# MOTORES.net
KiCad netlist of a schematic drawn in Altium Designer
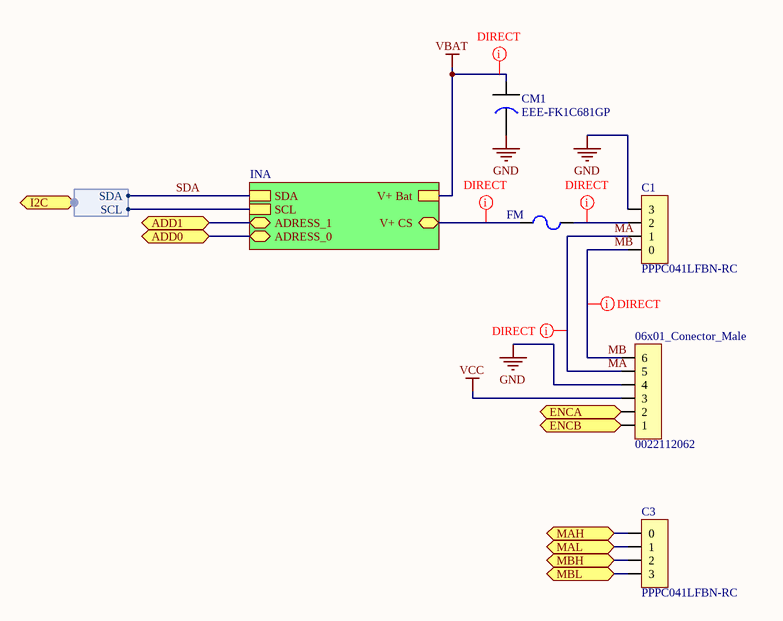
[diagram p0: MOTORES.SchDoc]

(export (version "E")
  (design (tool "Eeschema 10.0.6"))
  (components
    (comp (ref "06x01_Conector_Male")
      (value "0022112062")
      (footprint "06x01_Conector_Male")
      (description "CONN HEADER 6POS .100 VERT GOLD")
      (libsource (lib "Schlib1") (part "06x01_Conector_Male"))
    )
    (comp (ref "C1")
      (value "PPPC041LFBN-RC")
      (footprint "04x01_Conector_Female")
      (description "4 Position Header Connector 0.100\" (2.54mm) Through Hole Gold")
      (libsource (lib "Schlib1") (part "04x01_Conector_Female-SCH"))
    )
    (comp (ref "C3")
      (value "PPPC041LFBN-RC")
      (footprint "04x01_Conector_Female")
      (description "4 Position Header Connector 0.100\" (2.54mm) Through Hole Gold")
      (libsource (lib "") (part "04x01_Conector_Female-SCH_1"))
    )
    (comp (ref "CM1")
      (value "EEE-FK1C681GP")
      (footprint "EEE-FK1C681GP")
      (description "Aluminum Electrolytic Capacitors - SMD Al Lytic Cap SMT FK Series 105C")
      (libsource (lib "Schlib1") (part "CAP AL 680UF/16V"))
    )
    (comp (ref "FM")
      (value "MF-MSMF250/16X")
      (footprint "RESC4632X16N")
      (description "PTC RESETTABLE .30A 30V 1812")
      (libsource (lib "IMBEL") (part "MF-MSMF250/16X-01.A.1"))
    )
  )
  (nets
    (net (code "4") (name "/ENCA") (class "Default")
      (node (ref "06x01_Conector_Male") (pin "2") (pinfunction "2_2") (pintype "passive"))
    )
    (net (code "5") (name "/ENCB") (class "Default")
      (node (ref "06x01_Conector_Male") (pin "1") (pinfunction "1_1") (pintype "passive"))
    )
    (net (code "6") (name "/MA") (class "Default")
      (node (ref "06x01_Conector_Male") (pin "5") (pinfunction "5_5") (pintype "passive"))
      (node (ref "C1") (pin "1") (pinfunction "1_1") (pintype "passive"))
    )
    (net (code "7") (name "/MAH") (class "Default")
      (node (ref "C3") (pin "0") (pinfunction "0_0") (pintype "passive"))
    )
    (net (code "8") (name "/MAL") (class "Default")
      (node (ref "C3") (pin "1") (pinfunction "1_1") (pintype "passive"))
    )
    (net (code "9") (name "/MB") (class "Default")
      (node (ref "06x01_Conector_Male") (pin "6") (pinfunction "6_6") (pintype "passive"))
      (node (ref "C1") (pin "0") (pinfunction "0_0") (pintype "passive"))
    )
    (net (code "10") (name "/MBH") (class "Default")
      (node (ref "C3") (pin "2") (pinfunction "2_2") (pintype "passive"))
    )
    (net (code "11") (name "/MBL") (class "Default")
      (node (ref "C3") (pin "3") (pinfunction "3_3") (pintype "passive"))
    )
    (net (code "14") (name "/V+ CS") (class "Default")
      (node (ref "FM") (pin "2") (pinfunction "2_2") (pintype "passive"))
    )
    (net (code "16") (name "GND") (class "Default")
      (node (ref "06x01_Conector_Male") (pin "4") (pinfunction "4_4") (pintype "passive"))
      (node (ref "C1") (pin "3") (pinfunction "3_3") (pintype "passive"))
      (node (ref "CM1") (pin "2") (pinfunction "2_2") (pintype "passive"))
    )
    (net (code "17") (name "Net-(C1-Pad2)") (class "Default")
      (node (ref "C1") (pin "2") (pinfunction "2_2") (pintype "passive"))
      (node (ref "FM") (pin "1") (pinfunction "1_1") (pintype "passive"))
    )
    (net (code "18") (name "VBAT") (class "Default")
      (node (ref "CM1") (pin "1") (pinfunction "1_1") (pintype "passive"))
    )
    (net (code "19") (name "VCC") (class "Default")
      (node (ref "06x01_Conector_Male") (pin "3") (pinfunction "3_3") (pintype "passive"))
    )
  )
)
